# SIM-RELAY-2.net
KiCad netlist of a schematic drawn in EAGLE
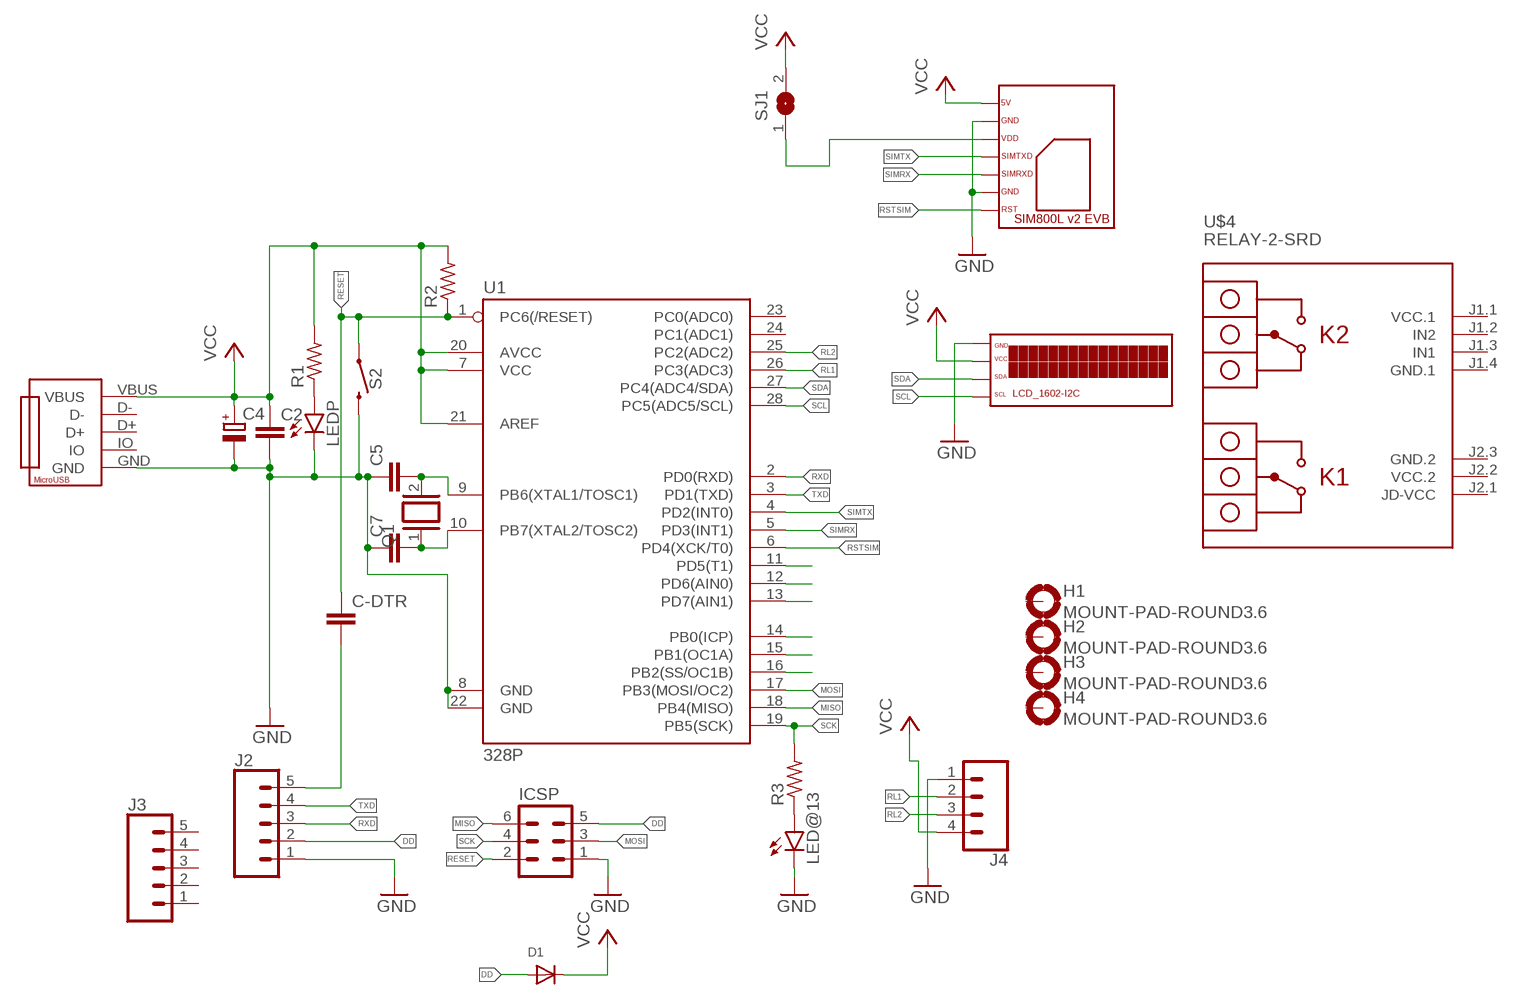
[diagram p0: schematic, sheet 1]

(export (version "E")
  (design (tool "Eeschema 10.0.6"))
  (components
    (comp (ref "C-DTR")
      (value "C-EU050-024X044")
      (footprint "eagle-import:C050-024X044")
      (libsource (lib "eagle-import") (part "C-EU050-024X044"))
    )
    (comp (ref "C2")
      (value "C-EU050-024X044")
      (footprint "eagle-import:C050-024X044")
      (libsource (lib "eagle-import") (part "C-EU050-024X044"))
    )
    (comp (ref "C4")
      (value "CPOL-EUB45181A")
      (footprint "eagle-import:B45181A")
      (libsource (lib "eagle-import") (part "CPOL-EUB45181A"))
    )
    (comp (ref "C5")
      (value "C-EU025-024X044")
      (footprint "eagle-import:C025-024X044")
      (libsource (lib "eagle-import") (part "C-EU025-024X044"))
    )
    (comp (ref "C7")
      (value "C-EU025-024X044")
      (footprint "eagle-import:C025-024X044")
      (libsource (lib "eagle-import") (part "C-EU025-024X044"))
    )
    (comp (ref "D1")
      (value "DIODESMA")
      (footprint "eagle-import:SMADIODE")
      (libsource (lib "eagle-import") (part "DIODESMA"))
    )
    (comp (ref "H1")
      (value "MOUNT-PAD-ROUND3.6")
      (footprint "eagle-import:3,6-PAD")
      (libsource (lib "eagle-import") (part "MOUNT-PAD-ROUND3.6"))
    )
    (comp (ref "H2")
      (value "MOUNT-PAD-ROUND3.6")
      (footprint "eagle-import:3,6-PAD")
      (libsource (lib "eagle-import") (part "MOUNT-PAD-ROUND3.6"))
    )
    (comp (ref "H3")
      (value "MOUNT-PAD-ROUND3.6")
      (footprint "eagle-import:3,6-PAD")
      (libsource (lib "eagle-import") (part "MOUNT-PAD-ROUND3.6"))
    )
    (comp (ref "H4")
      (value "MOUNT-PAD-ROUND3.6")
      (footprint "eagle-import:3,6-PAD")
      (libsource (lib "eagle-import") (part "MOUNT-PAD-ROUND3.6"))
    )
    (comp (ref "ICSP")
      (value "MA03-2")
      (footprint "eagle-import:MA03-2")
      (libsource (lib "eagle-import") (part "MA03-2"))
    )
    (comp (ref "J2")
      (value "CONN_05")
      (footprint "eagle-import:1X05")
      (libsource (lib "eagle-import") (part "CONN_05"))
    )
    (comp (ref "J3")
      (value "CONN_05")
      (footprint "eagle-import:1X05")
      (libsource (lib "eagle-import") (part "CONN_05"))
    )
    (comp (ref "J4")
      (value "CONN_04POLAR")
      (footprint "eagle-import:MOLEX-1X4")
      (libsource (lib "eagle-import") (part "CONN_04POLAR"))
    )
    (comp (ref "LED@13")
      (value "LED3MM")
      (footprint "eagle-import:LED3MM")
      (libsource (lib "eagle-import") (part "LED3MM"))
    )
    (comp (ref "LEDP")
      (value "LED3MM")
      (footprint "eagle-import:LED3MM")
      (libsource (lib "eagle-import") (part "LED3MM"))
    )
    (comp (ref "Q1")
      (value "XTAL/S")
      (footprint "eagle-import:QS")
      (libsource (lib "eagle-import") (part "XTAL/S"))
    )
    (comp (ref "R1")
      (value "R-US_R0805")
      (footprint "eagle-import:R0805")
      (libsource (lib "eagle-import") (part "R-US_R0805"))
    )
    (comp (ref "R2")
      (value "R-US_R0805")
      (footprint "eagle-import:R0805")
      (libsource (lib "eagle-import") (part "R-US_R0805"))
    )
    (comp (ref "R3")
      (value "R-US_R0805")
      (footprint "eagle-import:R0805")
      (libsource (lib "eagle-import") (part "R-US_R0805"))
    )
    (comp (ref "S2")
      (value "MOMENTARY-SWITCH-SPST-SMD-6.0X3.5MM")
      (footprint "eagle-import:TACTILE_SWITCH_SMD_6.0X3.5MM")
      (libsource (lib "eagle-import") (part "MOMENTARY-SWITCH-SPST-SMD-6.0X3.5MM"))
    )
    (comp (ref "SJ1") (value "SJ") (footprint "eagle-import:SJ") (libsource (lib "eagle-import") (part "SJ")))
    (comp (ref "U$1")
      (value "LCD1602-I2C")
      (footprint "eagle-import:1602-I2C")
      (libsource (lib "eagle-import") (part "LCD1602-I2C"))
    )
    (comp (ref "U$2")
      (value "SIM800V2")
      (footprint "eagle-import:SIM800V2")
      (libsource (lib "eagle-import") (part "SIM800V2"))
    )
    (comp (ref "U$4")
      (value "RELAY-2-SRD")
      (footprint "eagle-import:RELAY-2-SRD")
      (libsource (lib "eagle-import") (part "RELAY-2-SRD"))
    )
    (comp (ref "U$5")
      (value "MICROUSB-CONVERTER")
      (footprint "eagle-import:MICROUSB-CONV-1")
      (libsource (lib "eagle-import") (part "MICROUSB-CONVERTER"))
    )
    (comp (ref "U1")
      (value "328P")
      (footprint "eagle-import:DIP28")
      (libsource (lib "eagle-import") (part "ATMEGA328P_PDIP"))
    )
  )
  (nets
    (net (code "1") (name "/GND.1") (class "Default")
      (node (ref "U$4") (pin "J1.4") (pinfunction "GND.1_J1.4") (pintype "power_in"))
    )
    (net (code "2") (name "/GND.2") (class "Default")
      (node (ref "U$4") (pin "J2.3") (pinfunction "GND.2_J2.3") (pintype "power_in"))
    )
    (net (code "3") (name "/VCC.1") (class "Default")
      (node (ref "U$4") (pin "J1.1") (pinfunction "VCC.1_J1.1") (pintype "power_in"))
    )
    (net (code "4") (name "/VCC.2") (class "Default")
      (node (ref "U$4") (pin "J2.2") (pinfunction "VCC.2_J2.2") (pintype "power_in"))
    )
    (net (code "5") (name "DD") (class "Default")
      (node (ref "D1") (pin "A") (pinfunction "A_A") (pintype "passive"))
      (node (ref "ICSP") (pin "5") (pinfunction "5_5") (pintype "passive"))
      (node (ref "J2") (pin "2") (pinfunction "2_2") (pintype "passive"))
    )
    (net (code "6") (name "GND") (class "Default")
      (node (ref "C2") (pin "2") (pinfunction "2_2") (pintype "passive"))
      (node (ref "C4") (pin "-") (pinfunction "-_-") (pintype "passive"))
      (node (ref "C5") (pin "1") (pinfunction "1_1") (pintype "passive"))
      (node (ref "C7") (pin "1") (pinfunction "1_1") (pintype "passive"))
      (node (ref "ICSP") (pin "1") (pinfunction "1_1") (pintype "passive"))
      (node (ref "J2") (pin "1") (pinfunction "1_1") (pintype "passive"))
      (node (ref "J4") (pin "1") (pinfunction "1_1") (pintype "passive"))
      (node (ref "LED@13") (pin "K") (pinfunction "C_K") (pintype "passive"))
      (node (ref "LEDP") (pin "K") (pinfunction "C_K") (pintype "passive"))
      (node (ref "S2") (pin "2") (pinfunction "2_2") (pintype "passive"))
      (node (ref "U$1") (pin "GND") (pinfunction "GND_GND") (pintype "power_in"))
      (node (ref "U$2") (pin "GND") (pinfunction "GND_GND") (pintype "bidirectional"))
      (node (ref "U$2") (pin "GND2") (pinfunction "GND2_GND2") (pintype "bidirectional"))
      (node (ref "U$5") (pin "GND") (pinfunction "GND_GND") (pintype "bidirectional"))
      (node (ref "U1") (pin "22") (pinfunction "GND_22") (pintype "bidirectional"))
      (node (ref "U1") (pin "8") (pinfunction "GND_8") (pintype "bidirectional"))
    )
    (net (code "7") (name "MISO") (class "Default")
      (node (ref "ICSP") (pin "6") (pinfunction "6_6") (pintype "passive"))
      (node (ref "U1") (pin "18") (pinfunction "PB4(MISO)_18") (pintype "bidirectional"))
    )
    (net (code "8") (name "MOSI") (class "Default")
      (node (ref "ICSP") (pin "3") (pinfunction "3_3") (pintype "passive"))
      (node (ref "U1") (pin "17") (pinfunction "PB3(MOSI/OC2)_17") (pintype "bidirectional"))
    )
    (net (code "9") (name "Net-(C-DTR-Pad2)") (class "Default")
      (node (ref "C-DTR") (pin "2") (pinfunction "2_2") (pintype "passive"))
      (node (ref "J2") (pin "5") (pinfunction "5_5") (pintype "passive"))
    )
    (net (code "10") (name "Net-(LED@13-PadA)") (class "Default")
      (node (ref "LED@13") (pin "A") (pinfunction "A_A") (pintype "passive"))
      (node (ref "R3") (pin "1") (pinfunction "1_1") (pintype "passive"))
    )
    (net (code "11") (name "Net-(LEDP-PadA)") (class "Default")
      (node (ref "LEDP") (pin "A") (pinfunction "A_A") (pintype "passive"))
      (node (ref "R1") (pin "1") (pinfunction "1_1") (pintype "passive"))
    )
    (net (code "12") (name "Net-(SJ1-Pad1)") (class "Default")
      (node (ref "SJ1") (pin "1") (pinfunction "1_1") (pintype "passive"))
      (node (ref "U$2") (pin "VDD") (pinfunction "VDD_VDD") (pintype "bidirectional"))
    )
    (net (code "13") (name "Net-(U1-PB6(XTAL1{slash}TOSC1))") (class "Default")
      (node (ref "C5") (pin "2") (pinfunction "2_2") (pintype "passive"))
      (node (ref "Q1") (pin "2") (pinfunction "2_2") (pintype "passive"))
      (node (ref "U1") (pin "9") (pinfunction "PB6(XTAL1/TOSC1)_9") (pintype "bidirectional"))
    )
    (net (code "14") (name "Net-(U1-PB7(XTAL2{slash}TOSC2))") (class "Default")
      (node (ref "C7") (pin "2") (pinfunction "2_2") (pintype "passive"))
      (node (ref "Q1") (pin "1") (pinfunction "1_1") (pintype "passive"))
      (node (ref "U1") (pin "10") (pinfunction "PB7(XTAL2/TOSC2)_10") (pintype "bidirectional"))
    )
    (net (code "15") (name "RESET") (class "Default")
      (node (ref "C-DTR") (pin "1") (pinfunction "1_1") (pintype "passive"))
      (node (ref "ICSP") (pin "2") (pinfunction "2_2") (pintype "passive"))
      (node (ref "R2") (pin "1") (pinfunction "1_1") (pintype "passive"))
      (node (ref "S2") (pin "1") (pinfunction "1_1") (pintype "passive"))
      (node (ref "U1") (pin "1") (pinfunction "PC6(/RESET)_1") (pintype "bidirectional"))
    )
    (net (code "16") (name "RL1") (class "Default")
      (node (ref "J4") (pin "2") (pinfunction "2_2") (pintype "passive"))
      (node (ref "U1") (pin "26") (pinfunction "PC3(ADC3)_26") (pintype "bidirectional"))
    )
    (net (code "17") (name "RL2") (class "Default")
      (node (ref "J4") (pin "3") (pinfunction "3_3") (pintype "passive"))
      (node (ref "U1") (pin "25") (pinfunction "PC2(ADC2)_25") (pintype "bidirectional"))
    )
    (net (code "18") (name "RSTSIM") (class "Default")
      (node (ref "U$2") (pin "RST") (pinfunction "RST_RST") (pintype "bidirectional"))
      (node (ref "U1") (pin "6") (pinfunction "PD4(XCK/T0)_6") (pintype "bidirectional"))
    )
    (net (code "19") (name "RXD") (class "Default")
      (node (ref "J2") (pin "3") (pinfunction "3_3") (pintype "passive"))
      (node (ref "U1") (pin "2") (pinfunction "PD0(RXD)_2") (pintype "bidirectional"))
    )
    (net (code "20") (name "SCK") (class "Default")
      (node (ref "ICSP") (pin "4") (pinfunction "4_4") (pintype "passive"))
      (node (ref "R3") (pin "2") (pinfunction "2_2") (pintype "passive"))
      (node (ref "U1") (pin "19") (pinfunction "PB5(SCK)_19") (pintype "bidirectional"))
    )
    (net (code "21") (name "SCL") (class "Default")
      (node (ref "U$1") (pin "SCL") (pinfunction "SCL_SCL") (pintype "bidirectional"))
      (node (ref "U1") (pin "28") (pinfunction "PC5(ADC5/SCL)_28") (pintype "bidirectional"))
    )
    (net (code "22") (name "SDA") (class "Default")
      (node (ref "U$1") (pin "SDA") (pinfunction "SDA_SDA") (pintype "bidirectional"))
      (node (ref "U1") (pin "27") (pinfunction "PC4(ADC4/SDA)_27") (pintype "bidirectional"))
    )
    (net (code "23") (name "SIMRX") (class "Default")
      (node (ref "U$2") (pin "SIMRXD") (pinfunction "SIMRXD_SIMRXD") (pintype "bidirectional"))
      (node (ref "U1") (pin "5") (pinfunction "PD3(INT1)_5") (pintype "bidirectional"))
    )
    (net (code "24") (name "SIMTX") (class "Default")
      (node (ref "U$2") (pin "SIMTXD") (pinfunction "SIMTXD_SIMTXD") (pintype "bidirectional"))
      (node (ref "U1") (pin "4") (pinfunction "PD2(INT0)_4") (pintype "bidirectional"))
    )
    (net (code "25") (name "TXD") (class "Default")
      (node (ref "J2") (pin "4") (pinfunction "4_4") (pintype "passive"))
      (node (ref "U1") (pin "3") (pinfunction "PD1(TXD)_3") (pintype "bidirectional"))
    )
    (net (code "26") (name "VCC") (class "Default")
      (node (ref "C2") (pin "1") (pinfunction "1_1") (pintype "passive"))
      (node (ref "C4") (pin "+") (pinfunction "+_+") (pintype "passive"))
      (node (ref "D1") (pin "C") (pinfunction "C_C") (pintype "passive"))
      (node (ref "J4") (pin "4") (pinfunction "4_4") (pintype "passive"))
      (node (ref "R1") (pin "2") (pinfunction "2_2") (pintype "passive"))
      (node (ref "R2") (pin "2") (pinfunction "2_2") (pintype "passive"))
      (node (ref "SJ1") (pin "2") (pinfunction "2_2") (pintype "passive"))
      (node (ref "U$1") (pin "VCC") (pinfunction "VCC_VCC") (pintype "power_in"))
      (node (ref "U$2") (pin "5V") (pinfunction "5V_5V") (pintype "bidirectional"))
      (node (ref "U$5") (pin "VBUS") (pinfunction "VBUS_VBUS") (pintype "bidirectional"))
      (node (ref "U1") (pin "20") (pinfunction "AVCC_20") (pintype "bidirectional"))
      (node (ref "U1") (pin "21") (pinfunction "AREF_21") (pintype "bidirectional"))
      (node (ref "U1") (pin "7") (pinfunction "VCC_7") (pintype "bidirectional"))
    )
    (net (code "27") (name "unconnected-(H1-MOUNT-PadB3,6)") (class "Default")
      (node (ref "H1") (pin "B3,6") (pinfunction "MOUNT_B3,6") (pintype "passive"))
    )
    (net (code "28") (name "unconnected-(H2-MOUNT-PadB3,6)") (class "Default")
      (node (ref "H2") (pin "B3,6") (pinfunction "MOUNT_B3,6") (pintype "passive"))
    )
    (net (code "29") (name "unconnected-(H3-MOUNT-PadB3,6)") (class "Default")
      (node (ref "H3") (pin "B3,6") (pinfunction "MOUNT_B3,6") (pintype "passive"))
    )
    (net (code "30") (name "unconnected-(H4-MOUNT-PadB3,6)") (class "Default")
      (node (ref "H4") (pin "B3,6") (pinfunction "MOUNT_B3,6") (pintype "passive"))
    )
    (net (code "31") (name "unconnected-(J3-Pad1)") (class "Default")
      (node (ref "J3") (pin "1") (pinfunction "1_1") (pintype "passive"))
    )
    (net (code "32") (name "unconnected-(J3-Pad2)") (class "Default")
      (node (ref "J3") (pin "2") (pinfunction "2_2") (pintype "passive"))
    )
    (net (code "33") (name "unconnected-(J3-Pad3)") (class "Default")
      (node (ref "J3") (pin "3") (pinfunction "3_3") (pintype "passive"))
    )
    (net (code "34") (name "unconnected-(J3-Pad4)") (class "Default")
      (node (ref "J3") (pin "4") (pinfunction "4_4") (pintype "passive"))
    )
    (net (code "35") (name "unconnected-(J3-Pad5)") (class "Default")
      (node (ref "J3") (pin "5") (pinfunction "5_5") (pintype "passive"))
    )
    (net (code "36") (name "unconnected-(U$4-IN1-PadJ1.3)") (class "Default")
      (node (ref "U$4") (pin "J1.3") (pinfunction "IN1_J1.3") (pintype "bidirectional"))
    )
    (net (code "37") (name "unconnected-(U$4-IN2-PadJ1.2)") (class "Default")
      (node (ref "U$4") (pin "J1.2") (pinfunction "IN2_J1.2") (pintype "bidirectional"))
    )
    (net (code "38") (name "unconnected-(U$4-JD-VCC-PadJ2.1)") (class "Default")
      (node (ref "U$4") (pin "J2.1") (pinfunction "JD-VCC_J2.1") (pintype "bidirectional"))
    )
    (net (code "39") (name "unconnected-(U$5-PadD+)") (class "Default")
      (node (ref "U$5") (pin "D+") (pinfunction "D+_D+") (pintype "bidirectional"))
    )
    (net (code "40") (name "unconnected-(U$5-PadD-)") (class "Default")
      (node (ref "U$5") (pin "D-") (pinfunction "D-_D-") (pintype "bidirectional"))
    )
    (net (code "41") (name "unconnected-(U$5-PadIO)") (class "Default")
      (node (ref "U$5") (pin "IO") (pinfunction "IO_IO") (pintype "bidirectional"))
    )
    (net (code "42") (name "unconnected-(U1-PB0(ICP)-Pad14)") (class "Default")
      (node (ref "U1") (pin "14") (pinfunction "PB0(ICP)_14") (pintype "bidirectional"))
    )
    (net (code "43") (name "unconnected-(U1-PB1(OC1A)-Pad15)") (class "Default")
      (node (ref "U1") (pin "15") (pinfunction "PB1(OC1A)_15") (pintype "bidirectional"))
    )
    (net (code "44") (name "unconnected-(U1-PB2(SS{slash}OC1B)-Pad16)") (class "Default")
      (node (ref "U1") (pin "16") (pinfunction "PB2(SS/OC1B)_16") (pintype "bidirectional"))
    )
    (net (code "45") (name "unconnected-(U1-PC0(ADC0)-Pad23)") (class "Default")
      (node (ref "U1") (pin "23") (pinfunction "PC0(ADC0)_23") (pintype "bidirectional"))
    )
    (net (code "46") (name "unconnected-(U1-PC1(ADC1)-Pad24)") (class "Default")
      (node (ref "U1") (pin "24") (pinfunction "PC1(ADC1)_24") (pintype "bidirectional"))
    )
    (net (code "47") (name "unconnected-(U1-PD5(T1)-Pad11)") (class "Default")
      (node (ref "U1") (pin "11") (pinfunction "PD5(T1)_11") (pintype "bidirectional"))
    )
    (net (code "48") (name "unconnected-(U1-PD6(AIN0)-Pad12)") (class "Default")
      (node (ref "U1") (pin "12") (pinfunction "PD6(AIN0)_12") (pintype "bidirectional"))
    )
    (net (code "49") (name "unconnected-(U1-PD7(AIN1)-Pad13)") (class "Default")
      (node (ref "U1") (pin "13") (pinfunction "PD7(AIN1)_13") (pintype "bidirectional"))
    )
  )
)
